# circuit1_ver2.net
KiCad netlist of a schematic drawn in Altium Designer
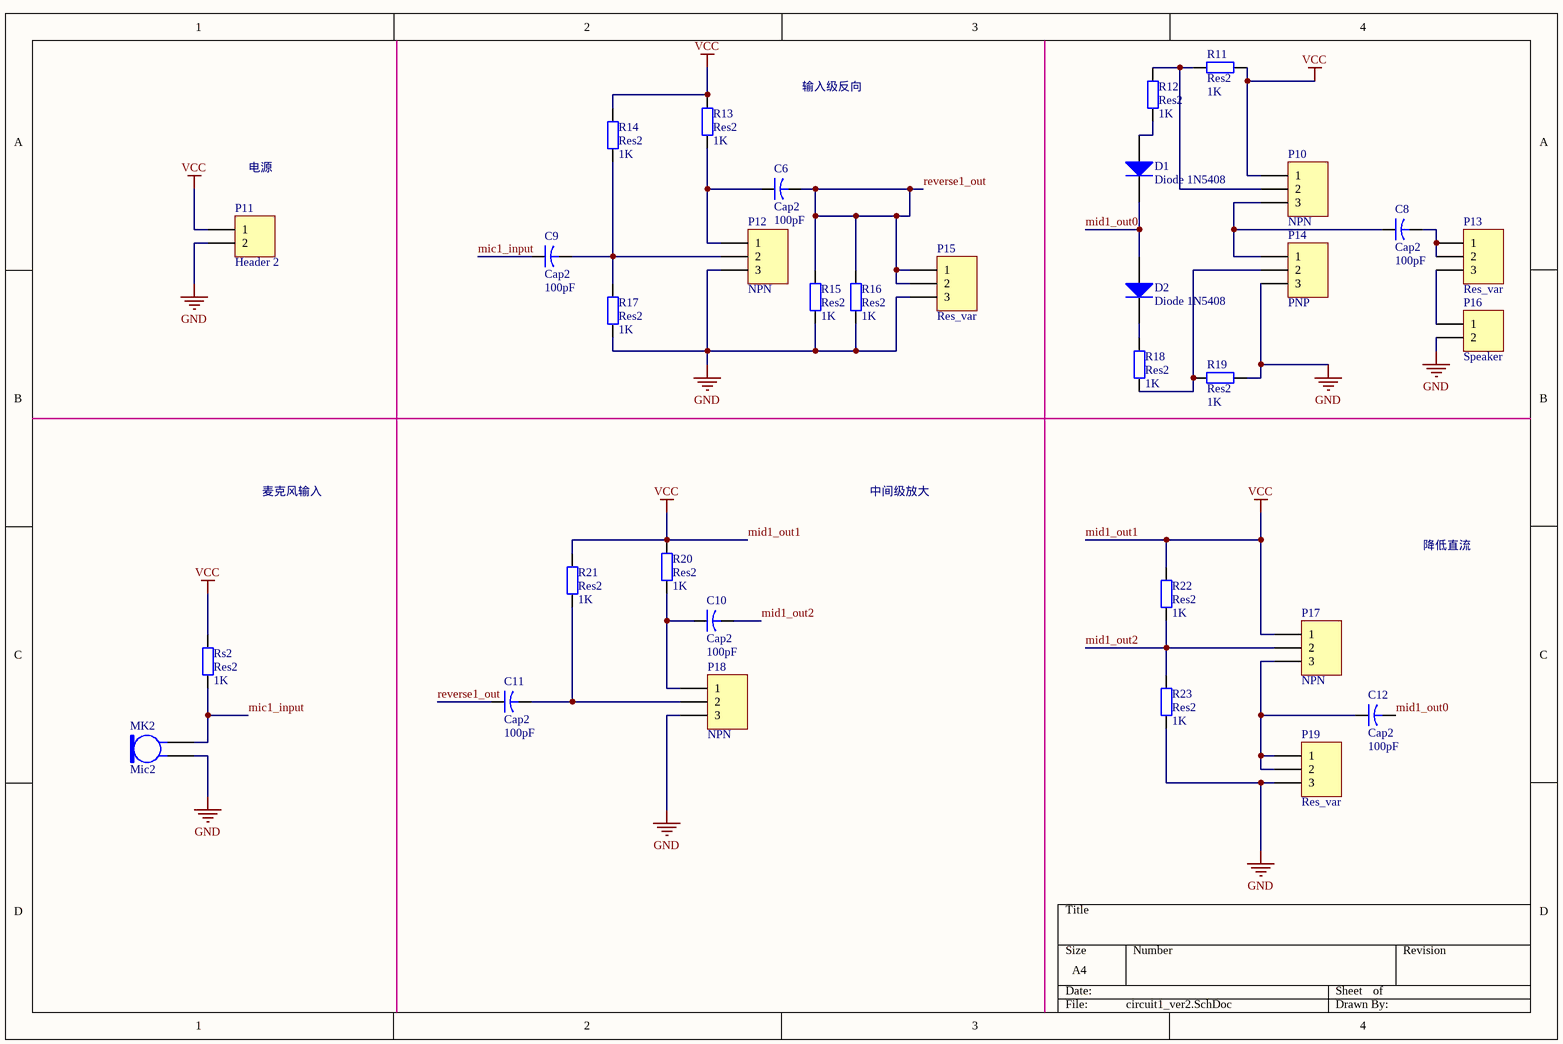
[diagram p0: circuit1_ver2.SchDoc]

(export (version "E")
  (design (tool "Eeschema 10.0.6"))
  (components
    (comp (ref "C6")
      (value "Cap2")
      (footprint "CAPR5-4X5")
      (description "Capacitor")
      (fields (field (name "ALTIUM_VALUE") "100pF") (field (name "PUBLISHER") "Altium Limited"))
      (libsource (lib "Miscellaneous Devices") (part "Cap2"))
    )
    (comp (ref "C8")
      (value "Cap2")
      (footprint "CAPR5-4X5")
      (description "Capacitor")
      (fields (field (name "ALTIUM_VALUE") "100pF") (field (name "PUBLISHER") "Altium Limited"))
      (libsource (lib "Miscellaneous Devices") (part "Cap2"))
    )
    (comp (ref "C9")
      (value "Cap2")
      (footprint "CAPR5-4X5")
      (description "Capacitor")
      (fields (field (name "ALTIUM_VALUE") "100pF") (field (name "PUBLISHER") "Altium Limited"))
      (libsource (lib "Miscellaneous Devices") (part "Cap2"))
    )
    (comp (ref "C10")
      (value "Cap2")
      (footprint "CAPR5-4X5")
      (description "Capacitor")
      (fields (field (name "ALTIUM_VALUE") "100pF") (field (name "PUBLISHER") "Altium Limited"))
      (libsource (lib "Miscellaneous Devices") (part "Cap2"))
    )
    (comp (ref "C11")
      (value "Cap2")
      (footprint "CAPR5-4X5")
      (description "Capacitor")
      (fields (field (name "ALTIUM_VALUE") "100pF") (field (name "PUBLISHER") "Altium Limited"))
      (libsource (lib "Miscellaneous Devices") (part "Cap2"))
    )
    (comp (ref "C12")
      (value "Cap2")
      (footprint "CAPR5-4X5")
      (description "Capacitor")
      (fields (field (name "ALTIUM_VALUE") "100pF") (field (name "PUBLISHER") "Altium Limited"))
      (libsource (lib "Miscellaneous Devices") (part "Cap2"))
    )
    (comp (ref "D1")
      (value "Diode 1N5408")
      (footprint "DO-201AD")
      (description "3 Amp Medium Power Silicon Rectifier Diode")
      (fields (field (name "PUBLISHER") "Altium Limited"))
      (libsource (lib "Miscellaneous Devices") (part "Diode 1N5408"))
    )
    (comp (ref "D2")
      (value "Diode 1N5408")
      (footprint "DO-201AD")
      (description "3 Amp Medium Power Silicon Rectifier Diode")
      (fields (field (name "PUBLISHER") "Altium Limited"))
      (libsource (lib "Miscellaneous Devices") (part "Diode 1N5408"))
    )
    (comp (ref "MK2")
      (value "Mic2")
      (footprint "PIN2")
      (description "Microphone")
      (fields (field (name "PUBLISHER") "Altium Limited"))
      (libsource (lib "Miscellaneous Devices") (part "Mic2"))
    )
    (comp (ref "P10")
      (value "NPN")
      (footprint "HDR1X3")
      (description "Header, 3-Pin")
      (fields (field (name "PUBLISHER") "Altium Limited"))
      (libsource (lib "Miscellaneous Connectors") (part "Header 3"))
    )
    (comp (ref "P11")
      (value "Header 2")
      (footprint "HDR1X2")
      (description "Header, 2-Pin")
      (fields (field (name "PUBLISHER") "Altium Limited"))
      (libsource (lib "Miscellaneous Connectors") (part "Header 2"))
    )
    (comp (ref "P12")
      (value "NPN")
      (footprint "HDR1X3")
      (description "Header, 3-Pin")
      (fields (field (name "PUBLISHER") "Altium Limited"))
      (libsource (lib "Miscellaneous Connectors") (part "Header 3"))
    )
    (comp (ref "P13")
      (value "Res_var")
      (footprint "HDR1X3")
      (description "Header, 3-Pin")
      (fields (field (name "PUBLISHER") "Altium Limited"))
      (libsource (lib "Miscellaneous Connectors") (part "Header 3"))
    )
    (comp (ref "P14")
      (value "PNP")
      (footprint "HDR1X3")
      (description "Header, 3-Pin")
      (fields (field (name "PUBLISHER") "Altium Limited"))
      (libsource (lib "Miscellaneous Connectors") (part "Header 3"))
    )
    (comp (ref "P15")
      (value "Res_var")
      (footprint "HDR1X3")
      (description "Header, 3-Pin")
      (fields (field (name "PUBLISHER") "Altium Limited"))
      (libsource (lib "Miscellaneous Connectors") (part "Header 3"))
    )
    (comp (ref "P16")
      (value "Speaker")
      (footprint "HDR1X2")
      (description "Header, 2-Pin")
      (fields (field (name "PUBLISHER") "Altium Limited"))
      (libsource (lib "Miscellaneous Connectors") (part "Header 2"))
    )
    (comp (ref "P17")
      (value "NPN")
      (footprint "HDR1X3")
      (description "Header, 3-Pin")
      (fields (field (name "PUBLISHER") "Altium Limited"))
      (libsource (lib "Miscellaneous Connectors") (part "Header 3"))
    )
    (comp (ref "P18")
      (value "NPN")
      (footprint "HDR1X3")
      (description "Header, 3-Pin")
      (fields (field (name "PUBLISHER") "Altium Limited"))
      (libsource (lib "Miscellaneous Connectors") (part "Header 3"))
    )
    (comp (ref "P19")
      (value "Res_var")
      (footprint "HDR1X3")
      (description "Header, 3-Pin")
      (fields (field (name "PUBLISHER") "Altium Limited"))
      (libsource (lib "Miscellaneous Connectors") (part "Header 3"))
    )
    (comp (ref "R11")
      (value "Res2")
      (footprint "AXIAL-0.4")
      (description "Resistor")
      (fields (field (name "ALTIUM_VALUE") "1K") (field (name "PUBLISHER") "Altium Limited"))
      (libsource (lib "") (part "Res2_1"))
    )
    (comp (ref "R12")
      (value "Res2")
      (footprint "AXIAL-0.4")
      (description "Resistor")
      (fields (field (name "ALTIUM_VALUE") "1K") (field (name "PUBLISHER") "Altium Limited"))
      (libsource (lib "Miscellaneous Devices") (part "Res2"))
    )
    (comp (ref "R13")
      (value "Res2")
      (footprint "AXIAL-0.4")
      (description "Resistor")
      (fields (field (name "ALTIUM_VALUE") "1K") (field (name "PUBLISHER") "Altium Limited"))
      (libsource (lib "Miscellaneous Devices") (part "Res2"))
    )
    (comp (ref "R14")
      (value "Res2")
      (footprint "AXIAL-0.4")
      (description "Resistor")
      (fields (field (name "ALTIUM_VALUE") "1K") (field (name "PUBLISHER") "Altium Limited"))
      (libsource (lib "Miscellaneous Devices") (part "Res2"))
    )
    (comp (ref "R15")
      (value "Res2")
      (footprint "AXIAL-0.4")
      (description "Resistor")
      (fields (field (name "ALTIUM_VALUE") "1K") (field (name "PUBLISHER") "Altium Limited"))
      (libsource (lib "Miscellaneous Devices") (part "Res2"))
    )
    (comp (ref "R16")
      (value "Res2")
      (footprint "AXIAL-0.4")
      (description "Resistor")
      (fields (field (name "ALTIUM_VALUE") "1K") (field (name "PUBLISHER") "Altium Limited"))
      (libsource (lib "Miscellaneous Devices") (part "Res2"))
    )
    (comp (ref "R17")
      (value "Res2")
      (footprint "AXIAL-0.4")
      (description "Resistor")
      (fields (field (name "ALTIUM_VALUE") "1K") (field (name "PUBLISHER") "Altium Limited"))
      (libsource (lib "Miscellaneous Devices") (part "Res2"))
    )
    (comp (ref "R18")
      (value "Res2")
      (footprint "AXIAL-0.4")
      (description "Resistor")
      (fields (field (name "ALTIUM_VALUE") "1K") (field (name "PUBLISHER") "Altium Limited"))
      (libsource (lib "Miscellaneous Devices") (part "Res2"))
    )
    (comp (ref "R19")
      (value "Res2")
      (footprint "AXIAL-0.4")
      (description "Resistor")
      (fields (field (name "ALTIUM_VALUE") "1K") (field (name "PUBLISHER") "Altium Limited"))
      (libsource (lib "") (part "Res2_1"))
    )
    (comp (ref "R20")
      (value "Res2")
      (footprint "AXIAL-0.4")
      (description "Resistor")
      (fields (field (name "ALTIUM_VALUE") "1K") (field (name "PUBLISHER") "Altium Limited"))
      (libsource (lib "Miscellaneous Devices") (part "Res2"))
    )
    (comp (ref "R21")
      (value "Res2")
      (footprint "AXIAL-0.4")
      (description "Resistor")
      (fields (field (name "ALTIUM_VALUE") "1K") (field (name "PUBLISHER") "Altium Limited"))
      (libsource (lib "Miscellaneous Devices") (part "Res2"))
    )
    (comp (ref "R22")
      (value "Res2")
      (footprint "AXIAL-0.4")
      (description "Resistor")
      (fields (field (name "ALTIUM_VALUE") "1K") (field (name "PUBLISHER") "Altium Limited"))
      (libsource (lib "Miscellaneous Devices") (part "Res2"))
    )
    (comp (ref "R23")
      (value "Res2")
      (footprint "AXIAL-0.4")
      (description "Resistor")
      (fields (field (name "ALTIUM_VALUE") "1K") (field (name "PUBLISHER") "Altium Limited"))
      (libsource (lib "Miscellaneous Devices") (part "Res2"))
    )
    (comp (ref "Rs2")
      (value "Res2")
      (footprint "AXIAL-0.4")
      (description "Resistor")
      (fields (field (name "ALTIUM_VALUE") "1K") (field (name "PUBLISHER") "Altium Limited"))
      (libsource (lib "Miscellaneous Devices") (part "Res2"))
    )
  )
  (nets
    (net (code "1") (name "/mic1_input") (class "Default")
      (node (ref "C9") (pin "1") (pinfunction "1_1") (pintype "passive"))
      (node (ref "MK2") (pin "2") (pinfunction "2_2") (pintype "passive"))
      (node (ref "Rs2") (pin "1") (pinfunction "1_1") (pintype "passive"))
    )
    (net (code "2") (name "/mid1_out0") (class "Default")
      (node (ref "C12") (pin "2") (pinfunction "2_2") (pintype "passive"))
      (node (ref "D1") (pin "2") (pinfunction "K_2") (pintype "passive"))
      (node (ref "D2") (pin "1") (pinfunction "A_1") (pintype "passive"))
    )
    (net (code "3") (name "/mid1_out2") (class "Default")
      (node (ref "C10") (pin "2") (pinfunction "2_2") (pintype "passive"))
      (node (ref "P17") (pin "2") (pinfunction "2_2") (pintype "passive"))
      (node (ref "R22") (pin "1") (pinfunction "1_1") (pintype "passive"))
      (node (ref "R23") (pin "2") (pinfunction "2_2") (pintype "passive"))
    )
    (net (code "4") (name "/reverse1_out") (class "Default")
      (node (ref "C11") (pin "1") (pinfunction "1_1") (pintype "passive"))
      (node (ref "C6") (pin "2") (pinfunction "2_2") (pintype "passive"))
      (node (ref "P15") (pin "1") (pinfunction "1_1") (pintype "passive"))
      (node (ref "P15") (pin "2") (pinfunction "2_2") (pintype "passive"))
      (node (ref "R15") (pin "2") (pinfunction "2_2") (pintype "passive"))
      (node (ref "R16") (pin "2") (pinfunction "2_2") (pintype "passive"))
    )
    (net (code "5") (name "GND") (class "Default")
      (node (ref "MK2") (pin "1") (pinfunction "1_1") (pintype "passive"))
      (node (ref "P11") (pin "2") (pinfunction "2_2") (pintype "passive"))
      (node (ref "P12") (pin "3") (pinfunction "3_3") (pintype "passive"))
      (node (ref "P14") (pin "3") (pinfunction "3_3") (pintype "passive"))
      (node (ref "P15") (pin "3") (pinfunction "3_3") (pintype "passive"))
      (node (ref "P16") (pin "2") (pinfunction "2_2") (pintype "passive"))
      (node (ref "P18") (pin "3") (pinfunction "3_3") (pintype "passive"))
      (node (ref "P19") (pin "3") (pinfunction "3_3") (pintype "passive"))
      (node (ref "R15") (pin "1") (pinfunction "1_1") (pintype "passive"))
      (node (ref "R16") (pin "1") (pinfunction "1_1") (pintype "passive"))
      (node (ref "R17") (pin "1") (pinfunction "1_1") (pintype "passive"))
      (node (ref "R19") (pin "1") (pinfunction "1_1") (pintype "passive"))
      (node (ref "R23") (pin "1") (pinfunction "1_1") (pintype "passive"))
    )
    (net (code "6") (name "Net-(C6-Pad1)") (class "Default")
      (node (ref "C6") (pin "1") (pinfunction "1_1") (pintype "passive"))
      (node (ref "P12") (pin "1") (pinfunction "1_1") (pintype "passive"))
      (node (ref "R13") (pin "1") (pinfunction "1_1") (pintype "passive"))
    )
    (net (code "7") (name "Net-(C8-Pad1)") (class "Default")
      (node (ref "C8") (pin "1") (pinfunction "1_1") (pintype "passive"))
      (node (ref "P10") (pin "3") (pinfunction "3_3") (pintype "passive"))
      (node (ref "P14") (pin "1") (pinfunction "1_1") (pintype "passive"))
    )
    (net (code "8") (name "Net-(C8-Pad2)") (class "Default")
      (node (ref "C8") (pin "2") (pinfunction "2_2") (pintype "passive"))
      (node (ref "P13") (pin "1") (pinfunction "1_1") (pintype "passive"))
      (node (ref "P13") (pin "2") (pinfunction "2_2") (pintype "passive"))
    )
    (net (code "9") (name "Net-(C9-Pad2)") (class "Default")
      (node (ref "C9") (pin "2") (pinfunction "2_2") (pintype "passive"))
      (node (ref "P12") (pin "2") (pinfunction "2_2") (pintype "passive"))
      (node (ref "R14") (pin "1") (pinfunction "1_1") (pintype "passive"))
      (node (ref "R17") (pin "2") (pinfunction "2_2") (pintype "passive"))
    )
    (net (code "10") (name "Net-(C10-Pad1)") (class "Default")
      (node (ref "C10") (pin "1") (pinfunction "1_1") (pintype "passive"))
      (node (ref "P18") (pin "1") (pinfunction "1_1") (pintype "passive"))
      (node (ref "R20") (pin "1") (pinfunction "1_1") (pintype "passive"))
    )
    (net (code "11") (name "Net-(C11-Pad2)") (class "Default")
      (node (ref "C11") (pin "2") (pinfunction "2_2") (pintype "passive"))
      (node (ref "P18") (pin "2") (pinfunction "2_2") (pintype "passive"))
      (node (ref "R21") (pin "1") (pinfunction "1_1") (pintype "passive"))
    )
    (net (code "12") (name "Net-(C12-Pad1)") (class "Default")
      (node (ref "C12") (pin "1") (pinfunction "1_1") (pintype "passive"))
      (node (ref "P17") (pin "3") (pinfunction "3_3") (pintype "passive"))
      (node (ref "P19") (pin "1") (pinfunction "1_1") (pintype "passive"))
      (node (ref "P19") (pin "2") (pinfunction "2_2") (pintype "passive"))
    )
    (net (code "13") (name "Net-(D1-A)") (class "Default")
      (node (ref "D1") (pin "1") (pinfunction "A_1") (pintype "passive"))
      (node (ref "R12") (pin "1") (pinfunction "1_1") (pintype "passive"))
    )
    (net (code "14") (name "Net-(D2-K)") (class "Default")
      (node (ref "D2") (pin "2") (pinfunction "K_2") (pintype "passive"))
      (node (ref "R18") (pin "2") (pinfunction "2_2") (pintype "passive"))
    )
    (net (code "15") (name "Net-(P10-Pad2)") (class "Default")
      (node (ref "P10") (pin "2") (pinfunction "2_2") (pintype "passive"))
      (node (ref "R11") (pin "2") (pinfunction "2_2") (pintype "passive"))
      (node (ref "R12") (pin "2") (pinfunction "2_2") (pintype "passive"))
    )
    (net (code "16") (name "Net-(P13-Pad3)") (class "Default")
      (node (ref "P13") (pin "3") (pinfunction "3_3") (pintype "passive"))
      (node (ref "P16") (pin "1") (pinfunction "1_1") (pintype "passive"))
    )
    (net (code "17") (name "Net-(P14-Pad2)") (class "Default")
      (node (ref "P14") (pin "2") (pinfunction "2_2") (pintype "passive"))
      (node (ref "R18") (pin "1") (pinfunction "1_1") (pintype "passive"))
      (node (ref "R19") (pin "2") (pinfunction "2_2") (pintype "passive"))
    )
    (net (code "18") (name "VCC") (class "Default")
      (node (ref "P10") (pin "1") (pinfunction "1_1") (pintype "passive"))
      (node (ref "P11") (pin "1") (pinfunction "1_1") (pintype "passive"))
      (node (ref "P17") (pin "1") (pinfunction "1_1") (pintype "passive"))
      (node (ref "R11") (pin "1") (pinfunction "1_1") (pintype "passive"))
      (node (ref "R13") (pin "2") (pinfunction "2_2") (pintype "passive"))
      (node (ref "R14") (pin "2") (pinfunction "2_2") (pintype "passive"))
      (node (ref "R20") (pin "2") (pinfunction "2_2") (pintype "passive"))
      (node (ref "R21") (pin "2") (pinfunction "2_2") (pintype "passive"))
      (node (ref "R22") (pin "2") (pinfunction "2_2") (pintype "passive"))
      (node (ref "Rs2") (pin "2") (pinfunction "2_2") (pintype "passive"))
    )
  )
)
